# Minimal_carrier_board_for_CM4_rev_B.net
KiCad netlist of a schematic drawn in EAGLE
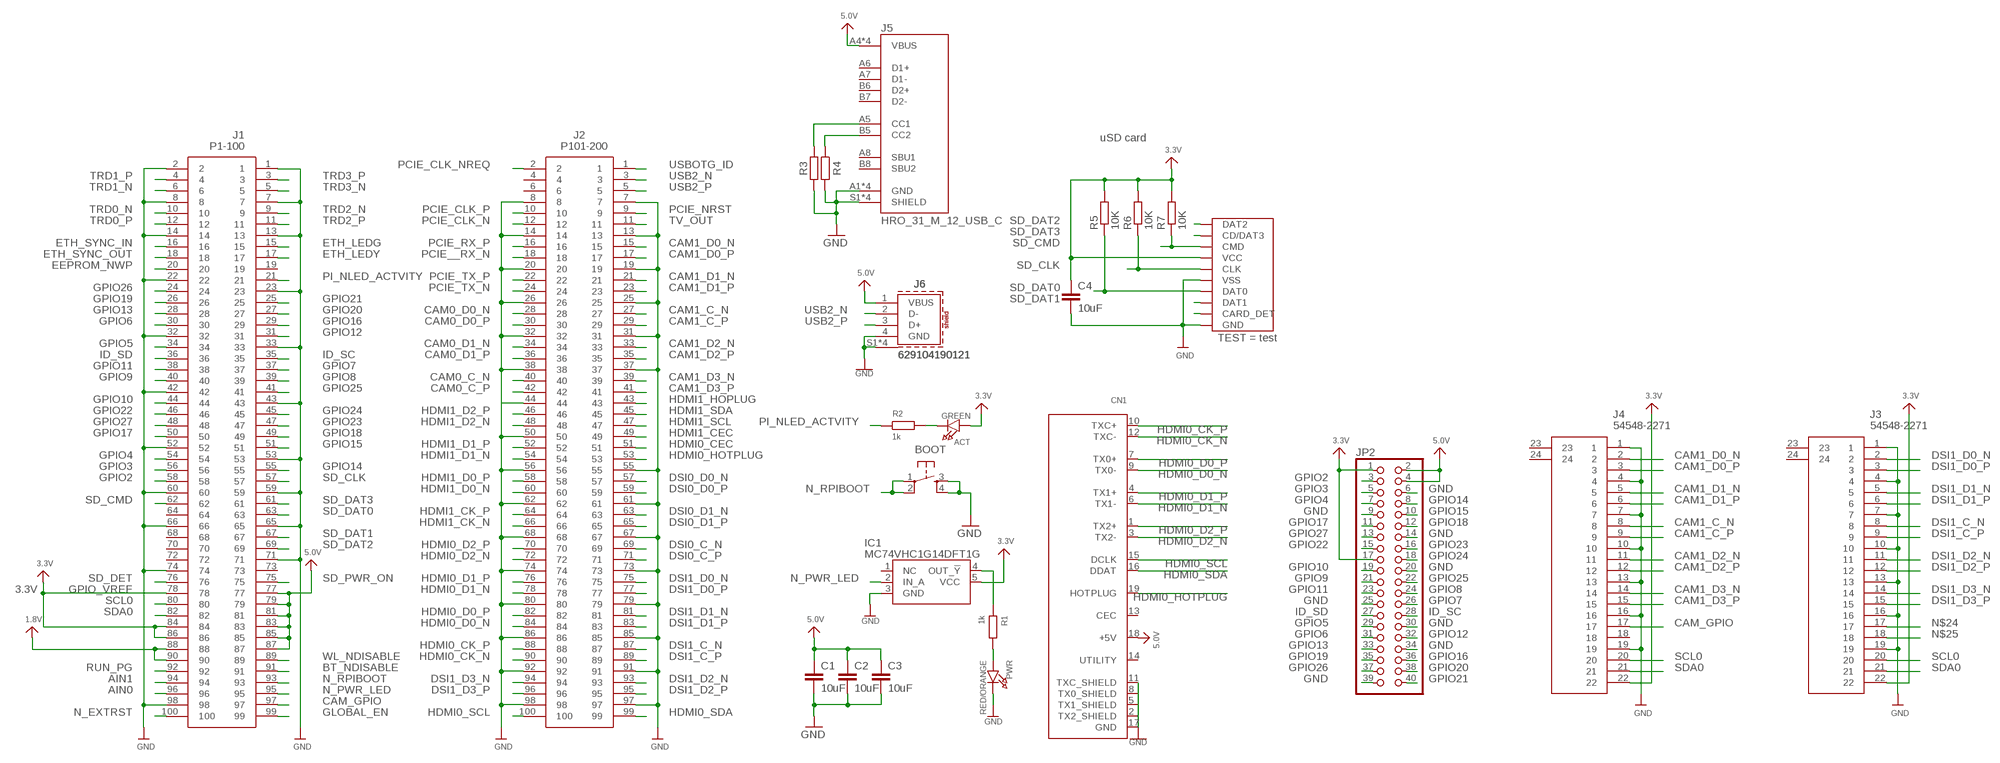
[diagram p0: schematic, sheet 1]

(export (version "E")
  (design (tool "Eeschema 10.0.6"))
  (components
    (comp (ref "ACT")
      (value "GREEN")
      (footprint "eagle-import:CHIPLED_0805_NOOUTLINE")
      (libsource (lib "eagle-import") (part "LED0805_NOOUTLINE"))
    )
    (comp (ref "BOOT")
      (value "TACTILE_SWITCHE_5X5_MICRO_")
      (footprint "eagle-import:TACTILE_SWITCH_5X5_MICRO")
      (libsource (lib "eagle-import") (part "TACTILE_SWITCHE_5X5_MICRO_"))
    )
    (comp (ref "C1")
      (value "10uF")
      (footprint "eagle-import:C0805")
      (libsource (lib "eagle-import") (part "C-EUC0805"))
    )
    (comp (ref "C2")
      (value "10uF")
      (footprint "eagle-import:C0805")
      (libsource (lib "eagle-import") (part "C-EUC0805"))
    )
    (comp (ref "C3")
      (value "10uF")
      (footprint "eagle-import:C0805")
      (libsource (lib "eagle-import") (part "C-EUC0805"))
    )
    (comp (ref "C4")
      (value "10uF")
      (footprint "eagle-import:C0805")
      (libsource (lib "eagle-import") (part "C-EUC0805"))
    )
    (comp (ref "CN1")
      (value "HDMI_MOLEX_47151-0001")
      (footprint "eagle-import:HDMI_MOLEX_47151-0001")
      (libsource (lib "eagle-import") (part "HDMI_MOLEX_47151-0001"))
    )
    (comp (ref "IC1")
      (value "MC74VHC1G14DFT1G")
      (footprint "eagle-import:SOT65P210X110-5N")
      (fields (field (name "MOUSER_PART_NUMBER") "863-MC74VHC1G14DFT1G"))
      (libsource (lib "eagle-import") (part "MC74VHC1G14DFT1G"))
    )
    (comp (ref "J1")
      (value "P1-100")
      (footprint "eagle-import:DF40C100DS04V51")
      (fields
        (field (name "ARROW_PART_NUMBER") "DF40C-100DS-0.4V(51)")
        (field (name "MOUSER_PART_NUMBER") "798-DF40C100DS0.4V51")
      )
      (libsource (lib "eagle-import") (part "DF40C-100DS-0.4V_51_"))
    )
    (comp (ref "J2")
      (value "P101-200")
      (footprint "eagle-import:DF40C100DS04V51")
      (fields
        (field (name "ARROW_PART_NUMBER") "DF40C-100DS-0.4V(51)")
        (field (name "MOUSER_PART_NUMBER") "798-DF40C100DS0.4V51")
      )
      (libsource (lib "eagle-import") (part "DF40C-100DS-0.4V_51_"))
    )
    (comp (ref "J3")
      (value "54548-2271")
      (footprint "eagle-import:545482271")
      (fields (field (name "MOUSER_PART_NUMBER") "538-54548-2271"))
      (libsource (lib "eagle-import") (part "54548-2271"))
    )
    (comp (ref "J4")
      (value "54548-2271")
      (footprint "eagle-import:545482271")
      (fields (field (name "MOUSER_PART_NUMBER") "538-54548-2271"))
      (libsource (lib "eagle-import") (part "54548-2271"))
    )
    (comp (ref "J5")
      (value "HRO_31_M_12_USB_C")
      (footprint "eagle-import:HRO_31_M_12_USB_C")
      (libsource (lib "eagle-import") (part "HRO_31_M_12_USB_C"))
    )
    (comp (ref "J6")
      (value "629104190121")
      (footprint "eagle-import:629104190121")
      (libsource (lib "eagle-import") (part "629104190121"))
    )
    (comp (ref "JP2")
      (value "PINHD-2X20")
      (footprint "eagle-import:2X20")
      (libsource (lib "eagle-import") (part "PINHD-2X20"))
    )
    (comp (ref "PWR")
      (value "RED/ORANGE")
      (footprint "eagle-import:CHIPLED_0805_NOOUTLINE")
      (libsource (lib "eagle-import") (part "LED0805_NOOUTLINE"))
    )
    (comp (ref "R1")
      (value "1k")
      (footprint "eagle-import:R0805")
      (libsource (lib "eagle-import") (part "R-EU_R0805"))
    )
    (comp (ref "R2")
      (value "1k")
      (footprint "eagle-import:R0805")
      (libsource (lib "eagle-import") (part "R-EU_R0805"))
    )
    (comp (ref "R3")
      (value "5.1k")
      (footprint "eagle-import:R0805")
      (libsource (lib "eagle-import") (part "R-EU_R0805"))
    )
    (comp (ref "R4")
      (value "5.1k")
      (footprint "eagle-import:R0805")
      (libsource (lib "eagle-import") (part "R-EU_R0805"))
    )
    (comp (ref "R5")
      (value "10K")
      (footprint "eagle-import:R0805")
      (libsource (lib "eagle-import") (part "R-EU_R0805"))
    )
    (comp (ref "R6")
      (value "10K")
      (footprint "eagle-import:R0805")
      (libsource (lib "eagle-import") (part "R-EU_R0805"))
    )
    (comp (ref "R7")
      (value "10K")
      (footprint "eagle-import:R0805")
      (libsource (lib "eagle-import") (part "R-EU_R0805"))
    )
    (comp (ref "SD_CARD")
      (value "MICRO_SD_CARD_")
      (footprint "eagle-import:TFP09-2--12B")
      (fields (field (name "TEST") "test"))
      (libsource (lib "eagle-import") (part "MICRO_SD_CARD_"))
    )
  )
  (nets
    (net (code "1") (name "/AIN0") (class "Default")
      (node (ref "J1") (pin "96") (pinfunction "96_96") (pintype "bidirectional"))
    )
    (net (code "2") (name "/AIN1") (class "Default")
      (node (ref "J1") (pin "94") (pinfunction "94_94") (pintype "bidirectional"))
    )
    (net (code "3") (name "/BT_NDISABLE") (class "Default")
      (node (ref "J1") (pin "91") (pinfunction "91_91") (pintype "bidirectional"))
    )
    (net (code "4") (name "/CAM0_C_N") (class "Default")
      (node (ref "J2") (pin "40") (pinfunction "40_40") (pintype "bidirectional"))
    )
    (net (code "5") (name "/CAM0_C_P") (class "Default")
      (node (ref "J2") (pin "42") (pinfunction "42_42") (pintype "bidirectional"))
    )
    (net (code "6") (name "/CAM0_D0_N") (class "Default")
      (node (ref "J2") (pin "28") (pinfunction "28_28") (pintype "bidirectional"))
    )
    (net (code "7") (name "/CAM0_D0_P") (class "Default")
      (node (ref "J2") (pin "30") (pinfunction "30_30") (pintype "bidirectional"))
    )
    (net (code "8") (name "/CAM0_D1_N") (class "Default")
      (node (ref "J2") (pin "34") (pinfunction "34_34") (pintype "bidirectional"))
    )
    (net (code "9") (name "/CAM0_D1_P") (class "Default")
      (node (ref "J2") (pin "36") (pinfunction "36_36") (pintype "bidirectional"))
    )
    (net (code "10") (name "/CAM1_C_N") (class "Default")
      (node (ref "J2") (pin "27") (pinfunction "27_27") (pintype "bidirectional"))
      (node (ref "J4") (pin "8") (pinfunction "8_8") (pintype "bidirectional"))
    )
    (net (code "11") (name "/CAM1_C_P") (class "Default")
      (node (ref "J2") (pin "29") (pinfunction "29_29") (pintype "bidirectional"))
      (node (ref "J4") (pin "9") (pinfunction "9_9") (pintype "bidirectional"))
    )
    (net (code "12") (name "/CAM1_D0_N") (class "Default")
      (node (ref "J2") (pin "15") (pinfunction "15_15") (pintype "bidirectional"))
      (node (ref "J4") (pin "2") (pinfunction "2_2") (pintype "bidirectional"))
    )
    (net (code "13") (name "/CAM1_D0_P") (class "Default")
      (node (ref "J2") (pin "17") (pinfunction "17_17") (pintype "bidirectional"))
      (node (ref "J4") (pin "3") (pinfunction "3_3") (pintype "bidirectional"))
    )
    (net (code "14") (name "/CAM1_D1_N") (class "Default")
      (node (ref "J2") (pin "21") (pinfunction "21_21") (pintype "bidirectional"))
      (node (ref "J4") (pin "5") (pinfunction "5_5") (pintype "bidirectional"))
    )
    (net (code "15") (name "/CAM1_D1_P") (class "Default")
      (node (ref "J2") (pin "23") (pinfunction "23_23") (pintype "bidirectional"))
      (node (ref "J4") (pin "6") (pinfunction "6_6") (pintype "bidirectional"))
    )
    (net (code "16") (name "/CAM1_D2_N") (class "Default")
      (node (ref "J2") (pin "33") (pinfunction "33_33") (pintype "bidirectional"))
      (node (ref "J4") (pin "11") (pinfunction "11_11") (pintype "bidirectional"))
    )
    (net (code "17") (name "/CAM1_D2_P") (class "Default")
      (node (ref "J2") (pin "35") (pinfunction "35_35") (pintype "bidirectional"))
      (node (ref "J4") (pin "12") (pinfunction "12_12") (pintype "bidirectional"))
    )
    (net (code "18") (name "/CAM1_D3_N") (class "Default")
      (node (ref "J2") (pin "39") (pinfunction "39_39") (pintype "bidirectional"))
      (node (ref "J4") (pin "14") (pinfunction "14_14") (pintype "bidirectional"))
    )
    (net (code "19") (name "/CAM1_D3_P") (class "Default")
      (node (ref "J2") (pin "41") (pinfunction "41_41") (pintype "bidirectional"))
      (node (ref "J4") (pin "15") (pinfunction "15_15") (pintype "bidirectional"))
    )
    (net (code "20") (name "/CAM_GPIO") (class "Default")
      (node (ref "J1") (pin "97") (pinfunction "97_97") (pintype "bidirectional"))
      (node (ref "J4") (pin "17") (pinfunction "17_17") (pintype "bidirectional"))
    )
    (net (code "21") (name "/DSI0_C_N") (class "Default")
      (node (ref "J2") (pin "69") (pinfunction "69_69") (pintype "bidirectional"))
    )
    (net (code "22") (name "/DSI0_C_P") (class "Default")
      (node (ref "J2") (pin "71") (pinfunction "71_71") (pintype "bidirectional"))
    )
    (net (code "23") (name "/DSI0_D0_N") (class "Default")
      (node (ref "J2") (pin "57") (pinfunction "57_57") (pintype "bidirectional"))
    )
    (net (code "24") (name "/DSI0_D0_P") (class "Default")
      (node (ref "J2") (pin "59") (pinfunction "59_59") (pintype "bidirectional"))
    )
    (net (code "25") (name "/DSI0_D1_N") (class "Default")
      (node (ref "J2") (pin "63") (pinfunction "63_63") (pintype "bidirectional"))
    )
    (net (code "26") (name "/DSI0_D1_P") (class "Default")
      (node (ref "J2") (pin "65") (pinfunction "65_65") (pintype "bidirectional"))
    )
    (net (code "27") (name "/DSI1_C_N") (class "Default")
      (node (ref "J2") (pin "87") (pinfunction "87_87") (pintype "bidirectional"))
      (node (ref "J3") (pin "8") (pinfunction "8_8") (pintype "bidirectional"))
    )
    (net (code "28") (name "/DSI1_C_P") (class "Default")
      (node (ref "J2") (pin "89") (pinfunction "89_89") (pintype "bidirectional"))
      (node (ref "J3") (pin "9") (pinfunction "9_9") (pintype "bidirectional"))
    )
    (net (code "29") (name "/DSI1_D0_N") (class "Default")
      (node (ref "J2") (pin "75") (pinfunction "75_75") (pintype "bidirectional"))
      (node (ref "J3") (pin "2") (pinfunction "2_2") (pintype "bidirectional"))
    )
    (net (code "30") (name "/DSI1_D0_P") (class "Default")
      (node (ref "J2") (pin "77") (pinfunction "77_77") (pintype "bidirectional"))
      (node (ref "J3") (pin "3") (pinfunction "3_3") (pintype "bidirectional"))
    )
    (net (code "31") (name "/DSI1_D1_N") (class "Default")
      (node (ref "J2") (pin "81") (pinfunction "81_81") (pintype "bidirectional"))
      (node (ref "J3") (pin "5") (pinfunction "5_5") (pintype "bidirectional"))
    )
    (net (code "32") (name "/DSI1_D1_P") (class "Default")
      (node (ref "J2") (pin "83") (pinfunction "83_83") (pintype "bidirectional"))
      (node (ref "J3") (pin "6") (pinfunction "6_6") (pintype "bidirectional"))
    )
    (net (code "33") (name "/DSI1_D2_N") (class "Default")
      (node (ref "J2") (pin "93") (pinfunction "93_93") (pintype "bidirectional"))
      (node (ref "J3") (pin "11") (pinfunction "11_11") (pintype "bidirectional"))
    )
    (net (code "34") (name "/DSI1_D2_P") (class "Default")
      (node (ref "J2") (pin "95") (pinfunction "95_95") (pintype "bidirectional"))
      (node (ref "J3") (pin "12") (pinfunction "12_12") (pintype "bidirectional"))
    )
    (net (code "35") (name "/DSI1_D3_N") (class "Default")
      (node (ref "J2") (pin "94") (pinfunction "94_94") (pintype "bidirectional"))
      (node (ref "J3") (pin "14") (pinfunction "14_14") (pintype "bidirectional"))
    )
    (net (code "36") (name "/DSI1_D3_P") (class "Default")
      (node (ref "J2") (pin "96") (pinfunction "96_96") (pintype "bidirectional"))
      (node (ref "J3") (pin "15") (pinfunction "15_15") (pintype "bidirectional"))
    )
    (net (code "37") (name "/EEPROM_NWP") (class "Default")
      (node (ref "J1") (pin "20") (pinfunction "20_20") (pintype "bidirectional"))
    )
    (net (code "38") (name "/ETH_LEDG") (class "Default")
      (node (ref "J1") (pin "15") (pinfunction "15_15") (pintype "bidirectional"))
    )
    (net (code "39") (name "/ETH_LEDY") (class "Default")
      (node (ref "J1") (pin "17") (pinfunction "17_17") (pintype "bidirectional"))
    )
    (net (code "40") (name "/ETH_SYNC_IN") (class "Default")
      (node (ref "J1") (pin "16") (pinfunction "16_16") (pintype "bidirectional"))
    )
    (net (code "41") (name "/ETH_SYNC_OUT") (class "Default")
      (node (ref "J1") (pin "18") (pinfunction "18_18") (pintype "bidirectional"))
    )
    (net (code "42") (name "/GLOBAL_EN") (class "Default")
      (node (ref "J1") (pin "99") (pinfunction "99_99") (pintype "bidirectional"))
    )
    (net (code "43") (name "/GPIO2") (class "Default")
      (node (ref "J1") (pin "58") (pinfunction "58_58") (pintype "bidirectional"))
      (node (ref "JP2") (pin "3") (pinfunction "3_3") (pintype "passive"))
    )
    (net (code "44") (name "/GPIO3") (class "Default")
      (node (ref "J1") (pin "56") (pinfunction "56_56") (pintype "bidirectional"))
      (node (ref "JP2") (pin "5") (pinfunction "5_5") (pintype "passive"))
    )
    (net (code "45") (name "/GPIO4") (class "Default")
      (node (ref "J1") (pin "54") (pinfunction "54_54") (pintype "bidirectional"))
      (node (ref "JP2") (pin "7") (pinfunction "7_7") (pintype "passive"))
    )
    (net (code "46") (name "/GPIO5") (class "Default")
      (node (ref "J1") (pin "34") (pinfunction "34_34") (pintype "bidirectional"))
      (node (ref "JP2") (pin "29") (pinfunction "29_29") (pintype "passive"))
    )
    (net (code "47") (name "/GPIO6") (class "Default")
      (node (ref "J1") (pin "30") (pinfunction "30_30") (pintype "bidirectional"))
      (node (ref "JP2") (pin "31") (pinfunction "31_31") (pintype "passive"))
    )
    (net (code "48") (name "/GPIO7") (class "Default")
      (node (ref "J1") (pin "37") (pinfunction "37_37") (pintype "bidirectional"))
      (node (ref "JP2") (pin "26") (pinfunction "26_26") (pintype "passive"))
    )
    (net (code "49") (name "/GPIO8") (class "Default")
      (node (ref "J1") (pin "39") (pinfunction "39_39") (pintype "bidirectional"))
      (node (ref "JP2") (pin "24") (pinfunction "24_24") (pintype "passive"))
    )
    (net (code "50") (name "/GPIO9") (class "Default")
      (node (ref "J1") (pin "40") (pinfunction "40_40") (pintype "bidirectional"))
      (node (ref "JP2") (pin "21") (pinfunction "21_21") (pintype "passive"))
    )
    (net (code "51") (name "/GPIO10") (class "Default")
      (node (ref "J1") (pin "44") (pinfunction "44_44") (pintype "bidirectional"))
      (node (ref "JP2") (pin "19") (pinfunction "19_19") (pintype "passive"))
    )
    (net (code "52") (name "/GPIO11") (class "Default")
      (node (ref "J1") (pin "38") (pinfunction "38_38") (pintype "bidirectional"))
      (node (ref "JP2") (pin "23") (pinfunction "23_23") (pintype "passive"))
    )
    (net (code "53") (name "/GPIO12") (class "Default")
      (node (ref "J1") (pin "31") (pinfunction "31_31") (pintype "bidirectional"))
      (node (ref "JP2") (pin "32") (pinfunction "32_32") (pintype "passive"))
    )
    (net (code "54") (name "/GPIO13") (class "Default")
      (node (ref "J1") (pin "28") (pinfunction "28_28") (pintype "bidirectional"))
      (node (ref "JP2") (pin "33") (pinfunction "33_33") (pintype "passive"))
    )
    (net (code "55") (name "/GPIO14") (class "Default")
      (node (ref "J1") (pin "55") (pinfunction "55_55") (pintype "bidirectional"))
      (node (ref "JP2") (pin "8") (pinfunction "8_8") (pintype "passive"))
    )
    (net (code "56") (name "/GPIO15") (class "Default")
      (node (ref "J1") (pin "51") (pinfunction "51_51") (pintype "bidirectional"))
      (node (ref "JP2") (pin "10") (pinfunction "10_10") (pintype "passive"))
    )
    (net (code "57") (name "/GPIO16") (class "Default")
      (node (ref "J1") (pin "29") (pinfunction "29_29") (pintype "bidirectional"))
      (node (ref "JP2") (pin "36") (pinfunction "36_36") (pintype "passive"))
    )
    (net (code "58") (name "/GPIO17") (class "Default")
      (node (ref "J1") (pin "50") (pinfunction "50_50") (pintype "bidirectional"))
      (node (ref "JP2") (pin "11") (pinfunction "11_11") (pintype "passive"))
    )
    (net (code "59") (name "/GPIO18") (class "Default")
      (node (ref "J1") (pin "49") (pinfunction "49_49") (pintype "bidirectional"))
      (node (ref "JP2") (pin "12") (pinfunction "12_12") (pintype "passive"))
    )
    (net (code "60") (name "/GPIO19") (class "Default")
      (node (ref "J1") (pin "26") (pinfunction "26_26") (pintype "bidirectional"))
      (node (ref "JP2") (pin "35") (pinfunction "35_35") (pintype "passive"))
    )
    (net (code "61") (name "/GPIO20") (class "Default")
      (node (ref "J1") (pin "27") (pinfunction "27_27") (pintype "bidirectional"))
      (node (ref "JP2") (pin "38") (pinfunction "38_38") (pintype "passive"))
    )
    (net (code "62") (name "/GPIO21") (class "Default")
      (node (ref "J1") (pin "25") (pinfunction "25_25") (pintype "bidirectional"))
      (node (ref "JP2") (pin "40") (pinfunction "40_40") (pintype "passive"))
    )
    (net (code "63") (name "/GPIO22") (class "Default")
      (node (ref "J1") (pin "46") (pinfunction "46_46") (pintype "bidirectional"))
      (node (ref "JP2") (pin "15") (pinfunction "15_15") (pintype "passive"))
    )
    (net (code "64") (name "/GPIO23") (class "Default")
      (node (ref "J1") (pin "47") (pinfunction "47_47") (pintype "bidirectional"))
      (node (ref "JP2") (pin "16") (pinfunction "16_16") (pintype "passive"))
    )
    (net (code "65") (name "/GPIO24") (class "Default")
      (node (ref "J1") (pin "45") (pinfunction "45_45") (pintype "bidirectional"))
      (node (ref "JP2") (pin "18") (pinfunction "18_18") (pintype "passive"))
    )
    (net (code "66") (name "/GPIO25") (class "Default")
      (node (ref "J1") (pin "41") (pinfunction "41_41") (pintype "bidirectional"))
      (node (ref "JP2") (pin "22") (pinfunction "22_22") (pintype "passive"))
    )
    (net (code "67") (name "/GPIO26") (class "Default")
      (node (ref "J1") (pin "24") (pinfunction "24_24") (pintype "bidirectional"))
      (node (ref "JP2") (pin "37") (pinfunction "37_37") (pintype "passive"))
    )
    (net (code "68") (name "/GPIO27") (class "Default")
      (node (ref "J1") (pin "48") (pinfunction "48_48") (pintype "bidirectional"))
      (node (ref "JP2") (pin "13") (pinfunction "13_13") (pintype "passive"))
    )
    (net (code "69") (name "/HDMI0_CEC") (class "Default")
      (node (ref "J2") (pin "51") (pinfunction "51_51") (pintype "bidirectional"))
    )
    (net (code "70") (name "/HDMI0_CK_N") (class "Default")
      (node (ref "CN1") (pin "12") (pinfunction "TXC-_12") (pintype "bidirectional"))
      (node (ref "J2") (pin "90") (pinfunction "90_90") (pintype "bidirectional"))
    )
    (net (code "71") (name "/HDMI0_CK_P") (class "Default")
      (node (ref "CN1") (pin "10") (pinfunction "TXC+_10") (pintype "bidirectional"))
      (node (ref "J2") (pin "88") (pinfunction "88_88") (pintype "bidirectional"))
    )
    (net (code "72") (name "/HDMI0_D0_N") (class "Default")
      (node (ref "CN1") (pin "9") (pinfunction "TX0-_9") (pintype "bidirectional"))
      (node (ref "J2") (pin "84") (pinfunction "84_84") (pintype "bidirectional"))
    )
    (net (code "73") (name "/HDMI0_D0_P") (class "Default")
      (node (ref "CN1") (pin "7") (pinfunction "TX0+_7") (pintype "bidirectional"))
      (node (ref "J2") (pin "82") (pinfunction "82_82") (pintype "bidirectional"))
    )
    (net (code "74") (name "/HDMI0_D1_N") (class "Default")
      (node (ref "CN1") (pin "6") (pinfunction "TX1-_6") (pintype "bidirectional"))
      (node (ref "J2") (pin "78") (pinfunction "78_78") (pintype "bidirectional"))
    )
    (net (code "75") (name "/HDMI0_D1_P") (class "Default")
      (node (ref "CN1") (pin "4") (pinfunction "TX1+_4") (pintype "bidirectional"))
      (node (ref "J2") (pin "76") (pinfunction "76_76") (pintype "bidirectional"))
    )
    (net (code "76") (name "/HDMI0_D2_N") (class "Default")
      (node (ref "CN1") (pin "3") (pinfunction "TX2-_3") (pintype "bidirectional"))
      (node (ref "J2") (pin "72") (pinfunction "72_72") (pintype "bidirectional"))
    )
    (net (code "77") (name "/HDMI0_D2_P") (class "Default")
      (node (ref "CN1") (pin "1") (pinfunction "TX2+_1") (pintype "bidirectional"))
      (node (ref "J2") (pin "70") (pinfunction "70_70") (pintype "bidirectional"))
    )
    (net (code "78") (name "/HDMI0_HOTPLUG") (class "Default")
      (node (ref "CN1") (pin "19") (pinfunction "HOTPLUG_19") (pintype "bidirectional"))
      (node (ref "J2") (pin "53") (pinfunction "53_53") (pintype "bidirectional"))
    )
    (net (code "79") (name "/HDMI0_SCL") (class "Default")
      (node (ref "CN1") (pin "15") (pinfunction "DCLK_15") (pintype "bidirectional"))
      (node (ref "J2") (pin "100") (pinfunction "100_100") (pintype "bidirectional"))
    )
    (net (code "80") (name "/HDMI0_SDA") (class "Default")
      (node (ref "CN1") (pin "16") (pinfunction "DDAT_16") (pintype "bidirectional"))
      (node (ref "J2") (pin "99") (pinfunction "99_99") (pintype "bidirectional"))
    )
    (net (code "81") (name "/HDMI1_CEC") (class "Default")
      (node (ref "J2") (pin "49") (pinfunction "49_49") (pintype "bidirectional"))
    )
    (net (code "82") (name "/HDMI1_CK_N") (class "Default")
      (node (ref "J2") (pin "66") (pinfunction "66_66") (pintype "bidirectional"))
    )
    (net (code "83") (name "/HDMI1_CK_P") (class "Default")
      (node (ref "J2") (pin "64") (pinfunction "64_64") (pintype "bidirectional"))
    )
    (net (code "84") (name "/HDMI1_D0_N") (class "Default")
      (node (ref "J2") (pin "60") (pinfunction "60_60") (pintype "bidirectional"))
    )
    (net (code "85") (name "/HDMI1_D0_P") (class "Default")
      (node (ref "J2") (pin "58") (pinfunction "58_58") (pintype "bidirectional"))
    )
    (net (code "86") (name "/HDMI1_D1_N") (class "Default")
      (node (ref "J2") (pin "54") (pinfunction "54_54") (pintype "bidirectional"))
    )
    (net (code "87") (name "/HDMI1_D1_P") (class "Default")
      (node (ref "J2") (pin "52") (pinfunction "52_52") (pintype "bidirectional"))
    )
    (net (code "88") (name "/HDMI1_D2_N") (class "Default")
      (node (ref "J2") (pin "48") (pinfunction "48_48") (pintype "bidirectional"))
    )
    (net (code "89") (name "/HDMI1_D2_P") (class "Default")
      (node (ref "J2") (pin "46") (pinfunction "46_46") (pintype "bidirectional"))
    )
    (net (code "90") (name "/HDMI1_HOPLUG") (class "Default")
      (node (ref "J2") (pin "43") (pinfunction "43_43") (pintype "bidirectional"))
    )
    (net (code "91") (name "/HDMI1_SCL") (class "Default")
      (node (ref "J2") (pin "47") (pinfunction "47_47") (pintype "bidirectional"))
    )
    (net (code "92") (name "/HDMI1_SDA") (class "Default")
      (node (ref "J2") (pin "45") (pinfunction "45_45") (pintype "bidirectional"))
    )
    (net (code "93") (name "/ID_SC") (class "Default")
      (node (ref "J1") (pin "35") (pinfunction "35_35") (pintype "bidirectional"))
      (node (ref "JP2") (pin "28") (pinfunction "28_28") (pintype "passive"))
    )
    (net (code "94") (name "/ID_SD") (class "Default")
      (node (ref "J1") (pin "36") (pinfunction "36_36") (pintype "bidirectional"))
      (node (ref "JP2") (pin "27") (pinfunction "27_27") (pintype "passive"))
    )
    (net (code "95") (name "/N$24") (class "Default")
      (node (ref "J3") (pin "17") (pinfunction "17_17") (pintype "bidirectional"))
    )
    (net (code "96") (name "/N$25") (class "Default")
      (node (ref "J3") (pin "18") (pinfunction "18_18") (pintype "bidirectional"))
    )
    (net (code "97") (name "/N_EXTRST") (class "Default")
      (node (ref "J1") (pin "100") (pinfunction "100_100") (pintype "bidirectional"))
    )
    (net (code "98") (name "/N_PWR_LED") (class "Default")
      (node (ref "IC1") (pin "2") (pinfunction "IN_A_2") (pintype "input"))
      (node (ref "J1") (pin "95") (pinfunction "95_95") (pintype "bidirectional"))
    )
    (net (code "99") (name "/N_RPIBOOT") (class "Default")
      (node (ref "BOOT") (pin "1") (pinfunction "1_1") (pintype "passive"))
      (node (ref "BOOT") (pin "2") (pinfunction "2_2") (pintype "passive"))
      (node (ref "J1") (pin "93") (pinfunction "93_93") (pintype "bidirectional"))
    )
    (net (code "100") (name "/PCIE_CLK_N") (class "Default")
      (node (ref "J2") (pin "12") (pinfunction "12_12") (pintype "bidirectional"))
    )
    (net (code "101") (name "/PCIE_CLK_NREQ") (class "Default")
      (node (ref "J2") (pin "2") (pinfunction "2_2") (pintype "bidirectional"))
    )
    (net (code "102") (name "/PCIE_CLK_P") (class "Default")
      (node (ref "J2") (pin "10") (pinfunction "10_10") (pintype "bidirectional"))
    )
    (net (code "103") (name "/PCIE_NRST") (class "Default")
      (node (ref "J2") (pin "9") (pinfunction "9_9") (pintype "bidirectional"))
    )
    (net (code "104") (name "/PCIE_RX_P") (class "Default")
      (node (ref "J2") (pin "16") (pinfunction "16_16") (pintype "bidirectional"))
    )
    (net (code "105") (name "/PCIE_TX_N") (class "Default")
      (node (ref "J2") (pin "24") (pinfunction "24_24") (pintype "bidirectional"))
    )
    (net (code "106") (name "/PCIE_TX_P") (class "Default")
      (node (ref "J2") (pin "22") (pinfunction "22_22") (pintype "bidirectional"))
    )
    (net (code "107") (name "/PCIE__RX_N") (class "Default")
      (node (ref "J2") (pin "18") (pinfunction "18_18") (pintype "bidirectional"))
    )
    (net (code "108") (name "/PI_NLED_ACTVITY") (class "Default")
      (node (ref "J1") (pin "21") (pinfunction "21_21") (pintype "bidirectional"))
      (node (ref "R2") (pin "1") (pinfunction "1_1") (pintype "passive"))
    )
    (net (code "109") (name "/RUN_PG") (class "Default")
      (node (ref "J1") (pin "92") (pinfunction "92_92") (pintype "bidirectional"))
    )
    (net (code "110") (name "/SCL0") (class "Default")
      (node (ref "J1") (pin "80") (pinfunction "80_80") (pintype "bidirectional"))
      (node (ref "J3") (pin "20") (pinfunction "20_20") (pintype "bidirectional"))
      (node (ref "J4") (pin "20") (pinfunction "20_20") (pintype "bidirectional"))
    )
    (net (code "111") (name "/SDA0") (class "Default")
      (node (ref "J1") (pin "82") (pinfunction "82_82") (pintype "bidirectional"))
      (node (ref "J3") (pin "21") (pinfunction "21_21") (pintype "bidirectional"))
      (node (ref "J4") (pin "21") (pinfunction "21_21") (pintype "bidirectional"))
    )
    (net (code "112") (name "/SD_CLK") (class "Default")
      (node (ref "J1") (pin "57") (pinfunction "57_57") (pintype "bidirectional"))
      (node (ref "R6") (pin "1") (pinfunction "1_1") (pintype "passive"))
      (node (ref "SD_CARD") (pin "CLK") (pinfunction "CLK_CLK") (pintype "bidirectional"))
    )
    (net (code "113") (name "/SD_CMD") (class "Default")
      (node (ref "J1") (pin "62") (pinfunction "62_62") (pintype "bidirectional"))
      (node (ref "R7") (pin "1") (pinfunction "1_1") (pintype "passive"))
      (node (ref "SD_CARD") (pin "CMD") (pinfunction "CMD_CMD") (pintype "bidirectional"))
    )
    (net (code "114") (name "/SD_DAT0") (class "Default")
      (node (ref "J1") (pin "63") (pinfunction "63_63") (pintype "bidirectional"))
      (node (ref "R5") (pin "1") (pinfunction "1_1") (pintype "passive"))
      (node (ref "SD_CARD") (pin "DAT0") (pinfunction "DAT0_DAT0") (pintype "bidirectional"))
    )
    (net (code "115") (name "/SD_DAT1") (class "Default")
      (node (ref "J1") (pin "67") (pinfunction "67_67") (pintype "bidirectional"))
      (node (ref "SD_CARD") (pin "DAT1") (pinfunction "DAT1_DAT1") (pintype "bidirectional"))
    )
    (net (code "116") (name "/SD_DAT2") (class "Default")
      (node (ref "J1") (pin "69") (pinfunction "69_69") (pintype "bidirectional"))
      (node (ref "SD_CARD") (pin "DAT2") (pinfunction "DAT2_DAT2") (pintype "bidirectional"))
    )
    (net (code "117") (name "/SD_DAT3") (class "Default")
      (node (ref "J1") (pin "61") (pinfunction "61_61") (pintype "bidirectional"))
      (node (ref "SD_CARD") (pin "CD/DAT3") (pinfunction "CD/DAT3_CD/DAT3") (pintype "bidirectional"))
    )
    (net (code "118") (name "/SD_DET") (class "Default")
      (node (ref "J1") (pin "76") (pinfunction "76_76") (pintype "bidirectional"))
    )
    (net (code "119") (name "/SD_PWR_ON") (class "Default")
      (node (ref "J1") (pin "75") (pinfunction "75_75") (pintype "bidirectional"))
    )
    (net (code "120") (name "/TRD0_N") (class "Default")
      (node (ref "J1") (pin "10") (pinfunction "10_10") (pintype "bidirectional"))
    )
    (net (code "121") (name "/TRD0_P") (class "Default")
      (node (ref "J1") (pin "12") (pinfunction "12_12") (pintype "bidirectional"))
    )
    (net (code "122") (name "/TRD1_N") (class "Default")
      (node (ref "J1") (pin "6") (pinfunction "6_6") (pintype "bidirectional"))
    )
    (net (code "123") (name "/TRD1_P") (class "Default")
      (node (ref "J1") (pin "4") (pinfunction "4_4") (pintype "bidirectional"))
    )
    (net (code "124") (name "/TRD2_N") (class "Default")
      (node (ref "J1") (pin "9") (pinfunction "9_9") (pintype "bidirectional"))
    )
    (net (code "125") (name "/TRD2_P") (class "Default")
      (node (ref "J1") (pin "11") (pinfunction "11_11") (pintype "bidirectional"))
    )
    (net (code "126") (name "/TRD3_N") (class "Default")
      (node (ref "J1") (pin "5") (pinfunction "5_5") (pintype "bidirectional"))
    )
    (net (code "127") (name "/TRD3_P") (class "Default")
      (node (ref "J1") (pin "3") (pinfunction "3_3") (pintype "bidirectional"))
    )
    (net (code "128") (name "/TV_OUT") (class "Default")
      (node (ref "J2") (pin "11") (pinfunction "11_11") (pintype "bidirectional"))
    )
    (net (code "129") (name "/USB2_N") (class "Default")
      (node (ref "J2") (pin "3") (pinfunction "3_3") (pintype "bidirectional"))
      (node (ref "J6") (pin "2") (pinfunction "D-_2") (pintype "bidirectional"))
    )
    (net (code "130") (name "/USB2_P") (class "Default")
      (node (ref "J2") (pin "5") (pinfunction "5_5") (pintype "bidirectional"))
      (node (ref "J6") (pin "3") (pinfunction "D+_3") (pintype "bidirectional"))
    )
    (net (code "131") (name "/USBOTG_ID") (class "Default")
      (node (ref "J2") (pin "1") (pinfunction "1_1") (pintype "bidirectional"))
    )
    (net (code "132") (name "/WL_NDISABLE") (class "Default")
      (node (ref "J1") (pin "89") (pinfunction "89_89") (pintype "bidirectional"))
    )
    (net (code "133") (name "1.8V") (class "Default")
      (node (ref "J1") (pin "88") (pinfunction "88_88") (pintype "bidirectional"))
      (node (ref "J1") (pin "90") (pinfunction "90_90") (pintype "bidirectional"))
    )
    (net (code "134") (name "3.3V") (class "Default")
      (node (ref "ACT") (pin "A") (pinfunction "A_A") (pintype "passive"))
      (node (ref "C4") (pin "1") (pinfunction "1_1") (pintype "passive"))
      (node (ref "IC1") (pin "5") (pinfunction "VCC_5") (pintype "power_in"))
      (node (ref "J1") (pin "78") (pinfunction "78_78") (pintype "bidirectional"))
      (node (ref "J1") (pin "84") (pinfunction "84_84") (pintype "bidirectional"))
      (node (ref "J1") (pin "86") (pinfunction "86_86") (pintype "bidirectional"))
      (node (ref "J3") (pin "22") (pinfunction "22_22") (pintype "bidirectional"))
      (node (ref "J4") (pin "22") (pinfunction "22_22") (pintype "bidirectional"))
      (node (ref "JP2") (pin "1") (pinfunction "1_1") (pintype "passive"))
      (node (ref "JP2") (pin "17") (pinfunction "17_17") (pintype "passive"))
      (node (ref "R5") (pin "2") (pinfunction "2_2") (pintype "passive"))
      (node (ref "R6") (pin "2") (pinfunction "2_2") (pintype "passive"))
      (node (ref "R7") (pin "2") (pinfunction "2_2") (pintype "passive"))
      (node (ref "SD_CARD") (pin "VCC") (pinfunction "VCC_VCC") (pintype "bidirectional"))
    )
    (net (code "135") (name "5.0V") (class "Default")
      (node (ref "C1") (pin "1") (pinfunction "1_1") (pintype "passive"))
      (node (ref "C2") (pin "1") (pinfunction "1_1") (pintype "passive"))
      (node (ref "C3") (pin "1") (pinfunction "1_1") (pintype "passive"))
      (node (ref "CN1") (pin "18") (pinfunction "+5V_18") (pintype "power_in"))
      (node (ref "J1") (pin "77") (pinfunction "77_77") (pintype "bidirectional"))
      (node (ref "J1") (pin "79") (pinfunction "79_79") (pintype "bidirectional"))
      (node (ref "J1") (pin "81") (pinfunction "81_81") (pintype "bidirectional"))
      (node (ref "J1") (pin "83") (pinfunction "83_83") (pintype "bidirectional"))
      (node (ref "J1") (pin "85") (pinfunction "85_85") (pintype "bidirectional"))
      (node (ref "J1") (pin "87") (pinfunction "87_87") (pintype "bidirectional"))
      (node (ref "J5") (pin "A4") (pinfunction "VBUS_A4") (pintype "passive"))
      (node (ref "J5") (pin "A9") (pinfunction "VBUS_A9") (pintype "passive"))
      (node (ref "J5") (pin "B4") (pinfunction "VBUS_B4") (pintype "passive"))
      (node (ref "J5") (pin "B9") (pinfunction "VBUS_B9") (pintype "passive"))
      (node (ref "J6") (pin "1") (pinfunction "VBUS_1") (pintype "bidirectional"))
      (node (ref "JP2") (pin "2") (pinfunction "2_2") (pintype "passive"))
      (node (ref "JP2") (pin "4") (pinfunction "4_4") (pintype "passive"))
    )
    (net (code "136") (name "GND") (class "Default")
      (node (ref "BOOT") (pin "3") (pinfunction "3_3") (pintype "passive"))
      (node (ref "BOOT") (pin "4") (pinfunction "4_4") (pintype "passive"))
      (node (ref "C1") (pin "2") (pinfunction "2_2") (pintype "passive"))
      (node (ref "C2") (pin "2") (pinfunction "2_2") (pintype "passive"))
      (node (ref "C3") (pin "2") (pinfunction "2_2") (pintype "passive"))
      (node (ref "C4") (pin "2") (pinfunction "2_2") (pintype "passive"))
      (node (ref "CN1") (pin "11") (pinfunction "TXC_SHIELD_11") (pintype "power_in"))
      (node (ref "CN1") (pin "17") (pinfunction "GND_17") (pintype "power_in"))
      (node (ref "CN1") (pin "2") (pinfunction "TX2_SHIELD_2") (pintype "power_in"))
      (node (ref "CN1") (pin "5") (pinfunction "TX1_SHIELD_5") (pintype "power_in"))
      (node (ref "CN1") (pin "8") (pinfunction "TX0_SHIELD_8") (pintype "power_in"))
      (node (ref "IC1") (pin "3") (pinfunction "GND_3") (pintype "power_in"))
      (node (ref "J1") (pin "1") (pinfunction "1_1") (pintype "bidirectional"))
      (node (ref "J1") (pin "13") (pinfunction "13_13") (pintype "bidirectional"))
      (node (ref "J1") (pin "14") (pinfunction "14_14") (pintype "bidirectional"))
      (node (ref "J1") (pin "2") (pinfunction "2_2") (pintype "bidirectional"))
      (node (ref "J1") (pin "22") (pinfunction "22_22") (pintype "bidirectional"))
      (node (ref "J1") (pin "23") (pinfunction "23_23") (pintype "bidirectional"))
      (node (ref "J1") (pin "32") (pinfunction "32_32") (pintype "bidirectional"))
      (node (ref "J1") (pin "33") (pinfunction "33_33") (pintype "bidirectional"))
      (node (ref "J1") (pin "42") (pinfunction "42_42") (pintype "bidirectional"))
      (node (ref "J1") (pin "43") (pinfunction "43_43") (pintype "bidirectional"))
      (node (ref "J1") (pin "52") (pinfunction "52_52") (pintype "bidirectional"))
      (node (ref "J1") (pin "53") (pinfunction "53_53") (pintype "bidirectional"))
      (node (ref "J1") (pin "59") (pinfunction "59_59") (pintype "bidirectional"))
      (node (ref "J1") (pin "60") (pinfunction "60_60") (pintype "bidirectional"))
      (node (ref "J1") (pin "65") (pinfunction "65_65") (pintype "bidirectional"))
      (node (ref "J1") (pin "66") (pinfunction "66_66") (pintype "bidirectional"))
      (node (ref "J1") (pin "7") (pinfunction "7_7") (pintype "bidirectional"))
      (node (ref "J1") (pin "71") (pinfunction "71_71") (pintype "bidirectional"))
      (node (ref "J1") (pin "74") (pinfunction "74_74") (pintype "bidirectional"))
      (node (ref "J1") (pin "8") (pinfunction "8_8") (pintype "bidirectional"))
      (node (ref "J1") (pin "98") (pinfunction "98_98") (pintype "bidirectional"))
      (node (ref "J2") (pin "13") (pinfunction "13_13") (pintype "bidirectional"))
      (node (ref "J2") (pin "14") (pinfunction "14_14") (pintype "bidirectional"))
      (node (ref "J2") (pin "19") (pinfunction "19_19") (pintype "bidirectional"))
      (node (ref "J2") (pin "20") (pinfunction "20_20") (pintype "bidirectional"))
      (node (ref "J2") (pin "25") (pinfunction "25_25") (pintype "bidirectional"))
      (node (ref "J2") (pin "26") (pinfunction "26_26") (pintype "bidirectional"))
      (node (ref "J2") (pin "31") (pinfunction "31_31") (pintype "bidirectional"))
      (node (ref "J2") (pin "32") (pinfunction "32_32") (pintype "bidirectional"))
      (node (ref "J2") (pin "37") (pinfunction "37_37") (pintype "bidirectional"))
      (node (ref "J2") (pin "38") (pinfunction "38_38") (pintype "bidirectional"))
      (node (ref "J2") (pin "44") (pinfunction "44_44") (pintype "bidirectional"))
      (node (ref "J2") (pin "50") (pinfunction "50_50") (pintype "bidirectional"))
      (node (ref "J2") (pin "55") (pinfunction "55_55") (pintype "bidirectional"))
      (node (ref "J2") (pin "56") (pinfunction "56_56") (pintype "bidirectional"))
      (node (ref "J2") (pin "61") (pinfunction "61_61") (pintype "bidirectional"))
      (node (ref "J2") (pin "62") (pinfunction "62_62") (pintype "bidirectional"))
      (node (ref "J2") (pin "67") (pinfunction "67_67") (pintype "bidirectional"))
      (node (ref "J2") (pin "68") (pinfunction "68_68") (pintype "bidirectional"))
      (node (ref "J2") (pin "7") (pinfunction "7_7") (pintype "bidirectional"))
      (node (ref "J2") (pin "73") (pinfunction "73_73") (pintype "bidirectional"))
      (node (ref "J2") (pin "74") (pinfunction "74_74") (pintype "bidirectional"))
      (node (ref "J2") (pin "79") (pinfunction "79_79") (pintype "bidirectional"))
      (node (ref "J2") (pin "8") (pinfunction "8_8") (pintype "bidirectional"))
      (node (ref "J2") (pin "80") (pinfunction "80_80") (pintype "bidirectional"))
      (node (ref "J2") (pin "85") (pinfunction "85_85") (pintype "bidirectional"))
      (node (ref "J2") (pin "86") (pinfunction "86_86") (pintype "bidirectional"))
      (node (ref "J2") (pin "91") (pinfunction "91_91") (pintype "bidirectional"))
      (node (ref "J2") (pin "92") (pinfunction "92_92") (pintype "bidirectional"))
      (node (ref "J2") (pin "97") (pinfunction "97_97") (pintype "bidirectional"))
      (node (ref "J2") (pin "98") (pinfunction "98_98") (pintype "bidirectional"))
      (node (ref "J3") (pin "1") (pinfunction "1_1") (pintype "bidirectional"))
      (node (ref "J3") (pin "10") (pinfunction "10_10") (pintype "bidirectional"))
      (node (ref "J3") (pin "13") (pinfunction "13_13") (pintype "bidirectional"))
      (node (ref "J3") (pin "16") (pinfunction "16_16") (pintype "bidirectional"))
      (node (ref "J3") (pin "19") (pinfunction "19_19") (pintype "bidirectional"))
      (node (ref "J3") (pin "4") (pinfunction "4_4") (pintype "bidirectional"))
      (node (ref "J3") (pin "7") (pinfunction "7_7") (pintype "bidirectional"))
      (node (ref "J4") (pin "1") (pinfunction "1_1") (pintype "bidirectional"))
      (node (ref "J4") (pin "10") (pinfunction "10_10") (pintype "bidirectional"))
      (node (ref "J4") (pin "13") (pinfunction "13_13") (pintype "bidirectional"))
      (node (ref "J4") (pin "16") (pinfunction "16_16") (pintype "bidirectional"))
      (node (ref "J4") (pin "19") (pinfunction "19_19") (pintype "bidirectional"))
      (node (ref "J4") (pin "4") (pinfunction "4_4") (pintype "bidirectional"))
      (node (ref "J4") (pin "7") (pinfunction "7_7") (pintype "bidirectional"))
      (node (ref "J5") (pin "A1") (pinfunction "GND_A1") (pintype "passive"))
      (node (ref "J5") (pin "A12") (pinfunction "GND_A12") (pintype "passive"))
      (node (ref "J5") (pin "B1") (pinfunction "GND_B1") (pintype "passive"))
      (node (ref "J5") (pin "B12") (pinfunction "GND_B12") (pintype "passive"))
      (node (ref "J5") (pin "S1") (pinfunction "SHIELD_S1") (pintype "passive"))
      (node (ref "J5") (pin "S2") (pinfunction "SHIELD_S2") (pintype "passive"))
      (node (ref "J5") (pin "S3") (pinfunction "SHIELD_S3") (pintype "passive"))
      (node (ref "J5") (pin "S4") (pinfunction "SHIELD_S4") (pintype "passive"))
      (node (ref "J6") (pin "4") (pinfunction "GND_4") (pintype "bidirectional"))
      (node (ref "J6") (pin "S1") (pinfunction "SHIELD_S1") (pintype "bidirectional"))
      (node (ref "J6") (pin "S2") (pinfunction "SHIELD_S2") (pintype "bidirectional"))
      (node (ref "J6") (pin "S3") (pinfunction "SHIELD_S3") (pintype "bidirectional"))
      (node (ref "J6") (pin "S4") (pinfunction "SHIELD_S4") (pintype "bidirectional"))
      (node (ref "JP2") (pin "14") (pinfunction "14_14") (pintype "passive"))
      (node (ref "JP2") (pin "20") (pinfunction "20_20") (pintype "passive"))
      (node (ref "JP2") (pin "25") (pinfunction "25_25") (pintype "passive"))
      (node (ref "JP2") (pin "30") (pinfunction "30_30") (pintype "passive"))
      (node (ref "JP2") (pin "34") (pinfunction "34_34") (pintype "passive"))
      (node (ref "JP2") (pin "39") (pinfunction "39_39") (pintype "passive"))
      (node (ref "JP2") (pin "6") (pinfunction "6_6") (pintype "passive"))
      (node (ref "JP2") (pin "9") (pinfunction "9_9") (pintype "passive"))
      (node (ref "PWR") (pin "C") (pinfunction "C_C") (pintype "passive"))
      (node (ref "R3") (pin "1") (pinfunction "1_1") (pintype "passive"))
      (node (ref "R4") (pin "2") (pinfunction "2_2") (pintype "passive"))
      (node (ref "SD_CARD") (pin "GND") (pinfunction "GND_GND") (pintype "bidirectional"))
      (node (ref "SD_CARD") (pin "GND@1") (pinfunction "GND_GND@1") (pintype "bidirectional"))
      (node (ref "SD_CARD") (pin "GND@2") (pinfunction "GND_GND@2") (pintype "bidirectional"))
      (node (ref "SD_CARD") (pin "GND@3") (pinfunction "VSS_GND@3") (pintype "bidirectional"))
      (node (ref "SD_CARD") (pin "VSS") (pinfunction "GND_VSS") (pintype "bidirectional"))
    )
    (net (code "137") (name "Net-(ACT-PadC)") (class "Default")
      (node (ref "ACT") (pin "C") (pinfunction "C_C") (pintype "passive"))
      (node (ref "R2") (pin "2") (pinfunction "2_2") (pintype "passive"))
    )
    (net (code "138") (name "Net-(IC1-OUT_~{Y})") (class "Default")
      (node (ref "IC1") (pin "4") (pinfunction "OUT_~{Y}_4") (pintype "output"))
      (node (ref "R1") (pin "1") (pinfunction "1_1") (pintype "passive"))
    )
    (net (code "139") (name "Net-(J5-CC1)") (class "Default")
      (node (ref "J5") (pin "A5") (pinfunction "CC1_A5") (pintype "passive"))
      (node (ref "R3") (pin "2") (pinfunction "2_2") (pintype "passive"))
    )
    (net (code "140") (name "Net-(J5-CC2)") (class "Default")
      (node (ref "J5") (pin "B5") (pinfunction "CC2_B5") (pintype "passive"))
      (node (ref "R4") (pin "1") (pinfunction "1_1") (pintype "passive"))
    )
    (net (code "141") (name "Net-(PWR-PadA)") (class "Default")
      (node (ref "PWR") (pin "A") (pinfunction "A_A") (pintype "passive"))
      (node (ref "R1") (pin "2") (pinfunction "2_2") (pintype "passive"))
    )
    (net (code "142") (name "unconnected-(CN1A-CEC-Pad13)") (class "Default")
      (node (ref "CN1") (pin "13") (pinfunction "CEC_13") (pintype "bidirectional"))
    )
    (net (code "143") (name "unconnected-(CN1A-UTILITY-Pad14)") (class "Default")
      (node (ref "CN1") (pin "14") (pinfunction "UTILITY_14") (pintype "bidirectional"))
    )
    (net (code "144") (name "unconnected-(IC1-NC-Pad1)") (class "Default")
      (node (ref "IC1") (pin "1") (pinfunction "NC_1") (pintype "no_connect"))
    )
    (net (code "145") (name "unconnected-(J1-Pad19)") (class "Default")
      (node (ref "J1") (pin "19") (pinfunction "19_19") (pintype "bidirectional"))
    )
    (net (code "146") (name "unconnected-(J1-Pad64)") (class "Default")
      (node (ref "J1") (pin "64") (pinfunction "64_64") (pintype "bidirectional"))
    )
    (net (code "147") (name "unconnected-(J1-Pad68)") (class "Default")
      (node (ref "J1") (pin "68") (pinfunction "68_68") (pintype "bidirectional"))
    )
    (net (code "148") (name "unconnected-(J1-Pad70)") (class "Default")
      (node (ref "J1") (pin "70") (pinfunction "70_70") (pintype "bidirectional"))
    )
    (net (code "149") (name "unconnected-(J1-Pad72)") (class "Default")
      (node (ref "J1") (pin "72") (pinfunction "72_72") (pintype "bidirectional"))
    )
    (net (code "150") (name "unconnected-(J1-Pad73)") (class "Default")
      (node (ref "J1") (pin "73") (pinfunction "73_73") (pintype "bidirectional"))
    )
    (net (code "151") (name "unconnected-(J2-Pad4)") (class "Default")
      (node (ref "J2") (pin "4") (pinfunction "4_4") (pintype "bidirectional"))
    )
    (net (code "152") (name "unconnected-(J2-Pad6)") (class "Default")
      (node (ref "J2") (pin "6") (pinfunction "6_6") (pintype "bidirectional"))
    )
    (net (code "153") (name "unconnected-(J3-Pad23)") (class "Default")
      (node (ref "J3") (pin "23") (pinfunction "23_23") (pintype "bidirectional"))
    )
    (net (code "154") (name "unconnected-(J3-Pad24)") (class "Default")
      (node (ref "J3") (pin "24") (pinfunction "24_24") (pintype "bidirectional"))
    )
    (net (code "155") (name "unconnected-(J4-Pad18)") (class "Default")
      (node (ref "J4") (pin "18") (pinfunction "18_18") (pintype "bidirectional"))
    )
    (net (code "156") (name "unconnected-(J4-Pad23)") (class "Default")
      (node (ref "J4") (pin "23") (pinfunction "23_23") (pintype "bidirectional"))
    )
    (net (code "157") (name "unconnected-(J4-Pad24)") (class "Default")
      (node (ref "J4") (pin "24") (pinfunction "24_24") (pintype "bidirectional"))
    )
    (net (code "158") (name "unconnected-(J5-D1+-PadA6)") (class "Default")
      (node (ref "J5") (pin "A6") (pinfunction "D1+_A6") (pintype "passive"))
    )
    (net (code "159") (name "unconnected-(J5-D1--PadA7)") (class "Default")
      (node (ref "J5") (pin "A7") (pinfunction "D1-_A7") (pintype "passive"))
    )
    (net (code "160") (name "unconnected-(J5-D2+-PadB6)") (class "Default")
      (node (ref "J5") (pin "B6") (pinfunction "D2+_B6") (pintype "passive"))
    )
    (net (code "161") (name "unconnected-(J5-D2--PadB7)") (class "Default")
      (node (ref "J5") (pin "B7") (pinfunction "D2-_B7") (pintype "passive"))
    )
    (net (code "162") (name "unconnected-(J5-SBU1-PadA8)") (class "Default")
      (node (ref "J5") (pin "A8") (pinfunction "SBU1_A8") (pintype "passive"))
    )
    (net (code "163") (name "unconnected-(J5-SBU2-PadB8)") (class "Default")
      (node (ref "J5") (pin "B8") (pinfunction "SBU2_B8") (pintype "passive"))
    )
    (net (code "164") (name "unconnected-(SD_CARD-CARD_DET-PadCD)") (class "Default")
      (node (ref "SD_CARD") (pin "CD") (pinfunction "CARD_DET_CD") (pintype "bidirectional"))
    )
  )
)
